# X7A15T-Prog.net
KiCad netlist of a schematic drawn in Altium Designer
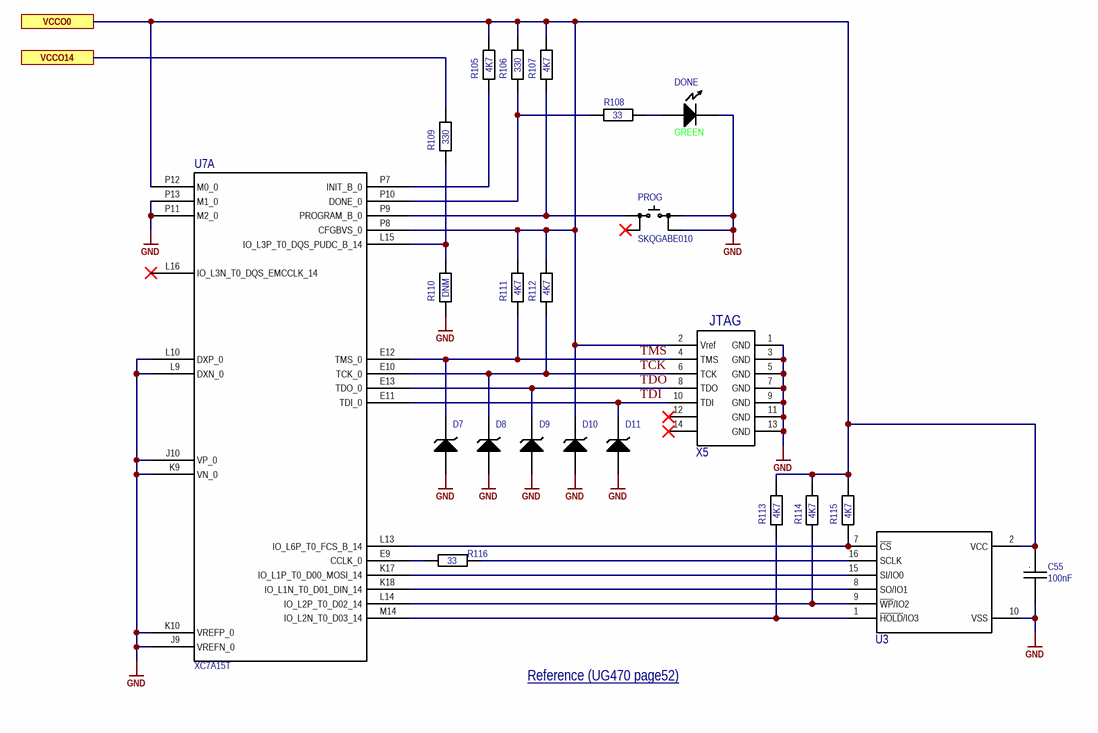
[diagram p0: X7A15T-Prog.SchDoc]

(export (version "E")
  (design (tool "Eeschema 10.0.6"))
  (components
    (comp (ref "C55")
      (value "100nF")
      (footprint "C0402 Reflow")
      (description "CAP CER 0.1UF 25V X7R 0402")
      (fields
        (field (name "TOLERANCE") "±5%")
        (field (name "02. DISTRIBUTOR PART NUMBER") "311-2077-6-ND")
        (field (name "13. CREATED DATE/NAME") "AUG2018/Hören")
      )
      (libsource (lib "chickenfood") (part "C"))
    )
    (comp (ref "D7")
      (value "D")
      (footprint "SOD323")
      (description "TVS DIODE 3.3V 9.5V SOD323")
      (fields
        (field (name "02. DISTRIBUTOR PART NUMBER") "UCLAMP3301DCT-ND")
        (field (name "07. MANUFACTURER  PART NUMBER") "UCLAMP3301D.TCT")
      )
      (libsource (lib "PCB-Tester-Board-V1") (part "UCLAMP3301D.TCT"))
    )
    (comp (ref "D8")
      (value "D")
      (footprint "SOD323")
      (description "TVS DIODE 3.3V 9.5V SOD323")
      (fields
        (field (name "02. DISTRIBUTOR PART NUMBER") "UCLAMP3301DCT-ND")
        (field (name "07. MANUFACTURER  PART NUMBER") "UCLAMP3301D.TCT")
      )
      (libsource (lib "PCB-Tester-Board-V1") (part "UCLAMP3301D.TCT"))
    )
    (comp (ref "D9")
      (value "D")
      (footprint "SOD323")
      (description "TVS DIODE 3.3V 9.5V SOD323")
      (fields
        (field (name "02. DISTRIBUTOR PART NUMBER") "UCLAMP3301DCT-ND")
        (field (name "07. MANUFACTURER  PART NUMBER") "UCLAMP3301D.TCT")
      )
      (libsource (lib "PCB-Tester-Board-V1") (part "UCLAMP3301D.TCT"))
    )
    (comp (ref "D10")
      (value "D")
      (footprint "SOD323")
      (description "TVS DIODE 3.3V 9.5V SOD323")
      (fields
        (field (name "02. DISTRIBUTOR PART NUMBER") "UCLAMP3301DCT-ND")
        (field (name "07. MANUFACTURER  PART NUMBER") "UCLAMP3301D.TCT")
      )
      (libsource (lib "PCB-Tester-Board-V1") (part "UCLAMP3301D.TCT"))
    )
    (comp (ref "D11")
      (value "D")
      (footprint "SOD323")
      (description "TVS DIODE 3.3V 9.5V SOD323")
      (fields
        (field (name "02. DISTRIBUTOR PART NUMBER") "UCLAMP3301DCT-ND")
        (field (name "07. MANUFACTURER  PART NUMBER") "UCLAMP3301D.TCT")
      )
      (libsource (lib "PCB-Tester-Board-V1") (part "UCLAMP3301D.TCT"))
    )
    (comp (ref "DONE")
      (value "D")
      (footprint "L0603G")
      (description "LED GREEN DIFFUSED 0603 SMD")
      (fields
        (field (name "02. DISTRIBUTOR PART NUMBER") "475-2709-6-ND")
        (field (name "07. MANUFACTURER  PART NUMBER") "LG L29K-G2J1-24-Z")
        (field (name "COLOR") "GREEN")
        (field (name "13. CREATED DATE/NAME") "AUG2018/Hören")
      )
      (libsource (lib "chickenfood") (part "LED"))
    )
    (comp (ref "PROG")
      (value "SKQGABE010")
      (footprint "SKQGABE010")
      (description "Tactile Switches 5.2x5.2x1.5mm 160gf")
      (fields (field (name "02. DISTRIBUTOR PART NUMBER") "688-SKQGAB"))
      (libsource (lib "PCB-Tester-Board-V1") (part "PUSH_BTN"))
    )
    (comp (ref "R105")
      (value "4K7")
      (footprint "R0402 Reflow")
      (description "RES SMD 4.7K OHM 1% 1/16W 0402")
      (fields
        (field (name "TOLERANCE") "±1%")
        (field (name "02. DISTRIBUTOR PART NUMBER") "311-4.7KLRDKR-ND")
        (field (name "13. CREATED DATE/NAME") "AUG2018/Hören")
      )
      (libsource (lib "chickenfood") (part "R"))
    )
    (comp (ref "R106")
      (value "330")
      (footprint "R0402 Reflow")
      (description "RES SMD 330 OHM 1% 1/16W 0402")
      (fields
        (field (name "TOLERANCE") "±1%")
        (field (name "02. DISTRIBUTOR PART NUMBER") "311-330LRDKR-ND")
        (field (name "13. CREATED DATE/NAME") "AUG2018/Hören")
      )
      (libsource (lib "chickenfood") (part "R"))
    )
    (comp (ref "R107")
      (value "4K7")
      (footprint "R0402 Reflow")
      (description "RES SMD 4.7K OHM 1% 1/16W 0402")
      (fields
        (field (name "TOLERANCE") "±1%")
        (field (name "02. DISTRIBUTOR PART NUMBER") "311-4.7KLRDKR-ND")
        (field (name "13. CREATED DATE/NAME") "AUG2018/Hören")
      )
      (libsource (lib "chickenfood") (part "R"))
    )
    (comp (ref "R108")
      (value "33")
      (footprint "R0402 Reflow")
      (description "RES SMD 33 OHM 1% 1/16W 0402")
      (fields
        (field (name "TOLERANCE") "±1%")
        (field (name "02. DISTRIBUTOR PART NUMBER") "311-33.0LRDKR-ND")
        (field (name "13. CREATED DATE/NAME") "AUG2018/Hören")
      )
      (libsource (lib "PCB-Tester-Board-V1") (part "R_19"))
    )
    (comp (ref "R109")
      (value "330")
      (footprint "R0402 Reflow")
      (description "RES SMD 330 OHM 1% 1/16W 0402")
      (fields
        (field (name "TOLERANCE") "±1%")
        (field (name "02. DISTRIBUTOR PART NUMBER") "311-330LRDKR-ND")
        (field (name "13. CREATED DATE/NAME") "AUG2018/Hören")
      )
      (libsource (lib "chickenfood") (part "R"))
    )
    (comp (ref "R110")
      (value "DNM")
      (footprint "R0402 Reflow")
      (description "RES SMD 330 OHM 1% 1/16W 0402")
      (fields
        (field (name "TOLERANCE") "±1%")
        (field (name "02. DISTRIBUTOR PART NUMBER") "311-330LRDKR-ND")
        (field (name "13. CREATED DATE/NAME") "AUG2018/Hören")
      )
      (libsource (lib "chickenfood") (part "R"))
    )
    (comp (ref "R111")
      (value "4K7")
      (footprint "R0402 Reflow")
      (description "RES SMD 4.7K OHM 1% 1/16W 0402")
      (fields
        (field (name "TOLERANCE") "±1%")
        (field (name "02. DISTRIBUTOR PART NUMBER") "311-4.7KLRDKR-ND")
        (field (name "13. CREATED DATE/NAME") "AUG2018/Hören")
      )
      (libsource (lib "chickenfood") (part "R"))
    )
    (comp (ref "R112")
      (value "4K7")
      (footprint "R0402 Reflow")
      (description "RES SMD 4.7K OHM 1% 1/16W 0402")
      (fields
        (field (name "TOLERANCE") "±1%")
        (field (name "02. DISTRIBUTOR PART NUMBER") "311-4.7KLRDKR-ND")
        (field (name "13. CREATED DATE/NAME") "AUG2018/Hören")
      )
      (libsource (lib "chickenfood") (part "R"))
    )
    (comp (ref "R113")
      (value "4K7")
      (footprint "R0402 Reflow")
      (description "RES SMD 4.7K OHM 1% 1/16W 0402")
      (fields
        (field (name "TOLERANCE") "±1%")
        (field (name "02. DISTRIBUTOR PART NUMBER") "311-4.7KLRDKR-ND")
        (field (name "13. CREATED DATE/NAME") "AUG2018/Hören")
      )
      (libsource (lib "chickenfood") (part "R"))
    )
    (comp (ref "R114")
      (value "4K7")
      (footprint "R0402 Reflow")
      (description "RES SMD 4.7K OHM 1% 1/16W 0402")
      (fields
        (field (name "TOLERANCE") "±1%")
        (field (name "02. DISTRIBUTOR PART NUMBER") "311-4.7KLRDKR-ND")
        (field (name "13. CREATED DATE/NAME") "AUG2018/Hören")
      )
      (libsource (lib "chickenfood") (part "R"))
    )
    (comp (ref "R115")
      (value "4K7")
      (footprint "R0402 Reflow")
      (description "RES SMD 4.7K OHM 1% 1/16W 0402")
      (fields
        (field (name "TOLERANCE") "±1%")
        (field (name "02. DISTRIBUTOR PART NUMBER") "311-4.7KLRDKR-ND")
        (field (name "13. CREATED DATE/NAME") "AUG2018/Hören")
      )
      (libsource (lib "chickenfood") (part "R"))
    )
    (comp (ref "R116")
      (value "33")
      (footprint "R0402 Reflow")
      (description "RES SMD 33 OHM 1% 1/16W 0402")
      (fields
        (field (name "TOLERANCE") "±1%")
        (field (name "02. DISTRIBUTOR PART NUMBER") "311-33.0LRDKR-ND")
        (field (name "13. CREATED DATE/NAME") "AUG2018/Hören")
      )
      (libsource (lib "PCB-Tester-Board-V1") (part "R_19"))
    )
    (comp (ref "U3")
      (value "U")
      (footprint "SOICW-16")
      (description "IC FLASH 128M SPI 133MHZ 16SOIC")
      (fields (field (name "02. DISTRIBUTOR PART NUMBER") "1274-1000-ND"))
      (libsource (lib "PCB-Tester-Board-V1") (part "S25FL128SAGMFI000"))
    )
    (comp (ref "U7")
      (value "U")
      (footprint "XC7A15T-1CSG324C")
      (description "XC7A15T-1CSG324C")
      (fields (field (name "MFR") "XILINX") (field (name "NICNAME") "XC7A15T"))
      (libsource (lib "PCB-Tester-Board-V1") (part "XC7A15T-CS324"))
    )
    (comp (ref "X5")
      (value "X")
      (footprint "LTMM-107-02-F-D")
      (description "CONN HEADER VERT 14POS 2MM")
      (fields
        (field (name "02. DISTRIBUTOR PART NUMBER") "LTMM-107-02-F-D-ND")
        (field (name "07. MANUFACTURER  PART NUMBER") "LTMM-107-02-F-D")
        (field (name "NICKNAME") "JTAG")
        (field (name "13. CREATED DATE/NAME") "??? / Hören")
      )
      (libsource (lib "Connectors") (part "LTMM-107-02-F-D"))
    )
  )
  (nets
    (net (code "1") (name "/TCK") (class "Default")
      (node (ref "D8") (pin "2") (pinfunction "C_2") (pintype "passive"))
      (node (ref "R112") (pin "1") (pinfunction "1_1") (pintype "passive"))
      (node (ref "U7") (pin "E10") (pinfunction "TCK_0_E10") (pintype "passive"))
      (node (ref "X5") (pin "6") (pinfunction "TCK_6") (pintype "passive"))
    )
    (net (code "2") (name "/TDI") (class "Default")
      (node (ref "D11") (pin "2") (pinfunction "C_2") (pintype "passive"))
      (node (ref "U7") (pin "E11") (pinfunction "TDI_0_E11") (pintype "passive"))
      (node (ref "X5") (pin "10") (pinfunction "TDI_10") (pintype "passive"))
    )
    (net (code "3") (name "/TDO") (class "Default")
      (node (ref "D9") (pin "2") (pinfunction "C_2") (pintype "passive"))
      (node (ref "U7") (pin "E13") (pinfunction "TDO_0_E13") (pintype "passive"))
      (node (ref "X5") (pin "8") (pinfunction "TDO_8") (pintype "passive"))
    )
    (net (code "4") (name "/TMS") (class "Default")
      (node (ref "D7") (pin "2") (pinfunction "C_2") (pintype "passive"))
      (node (ref "R111") (pin "1") (pinfunction "1_1") (pintype "passive"))
      (node (ref "U7") (pin "E12") (pinfunction "TMS_0_E12") (pintype "passive"))
      (node (ref "X5") (pin "4") (pinfunction "TMS_4") (pintype "passive"))
    )
    (net (code "5") (name "/VCCO0") (class "Default")
      (node (ref "C55") (pin "1") (pinfunction "1_1") (pintype "passive"))
      (node (ref "D10") (pin "2") (pinfunction "C_2") (pintype "passive"))
      (node (ref "R105") (pin "2") (pinfunction "2_2") (pintype "passive"))
      (node (ref "R106") (pin "2") (pinfunction "2_2") (pintype "passive"))
      (node (ref "R107") (pin "2") (pinfunction "2_2") (pintype "passive"))
      (node (ref "R111") (pin "2") (pinfunction "2_2") (pintype "passive"))
      (node (ref "R112") (pin "2") (pinfunction "2_2") (pintype "passive"))
      (node (ref "R113") (pin "2") (pinfunction "2_2") (pintype "passive"))
      (node (ref "R114") (pin "2") (pinfunction "2_2") (pintype "passive"))
      (node (ref "R115") (pin "2") (pinfunction "2_2") (pintype "passive"))
      (node (ref "U3") (pin "2") (pinfunction "VCC_2") (pintype "passive"))
      (node (ref "U7") (pin "P12") (pinfunction "M0_0_P12") (pintype "passive"))
      (node (ref "U7") (pin "P8") (pinfunction "CFGBVS_0_P8") (pintype "passive"))
      (node (ref "X5") (pin "2") (pinfunction "Vref_2") (pintype "passive"))
    )
    (net (code "6") (name "/VCCO14") (class "Default")
      (node (ref "R109") (pin "2") (pinfunction "2_2") (pintype "passive"))
    )
    (net (code "7") (name "GND") (class "Default")
      (node (ref "C55") (pin "2") (pinfunction "2_2") (pintype "passive"))
      (node (ref "D10") (pin "1") (pinfunction "A_1") (pintype "passive"))
      (node (ref "D11") (pin "1") (pinfunction "A_1") (pintype "passive"))
      (node (ref "D7") (pin "1") (pinfunction "A_1") (pintype "passive"))
      (node (ref "D8") (pin "1") (pinfunction "A_1") (pintype "passive"))
      (node (ref "D9") (pin "1") (pinfunction "A_1") (pintype "passive"))
      (node (ref "DONE") (pin "2") (pinfunction "Cathode_2") (pintype "passive"))
      (node (ref "PROG") (pin "3") (pinfunction "3_3") (pintype "passive"))
      (node (ref "PROG") (pin "4") (pinfunction "4_4") (pintype "passive"))
      (node (ref "R110") (pin "1") (pinfunction "1_1") (pintype "passive"))
      (node (ref "U3") (pin "10") (pinfunction "VSS_10") (pintype "passive"))
      (node (ref "U7") (pin "J10") (pinfunction "VP_0_J10") (pintype "passive"))
      (node (ref "U7") (pin "J9") (pinfunction "VREFN_0_J9") (pintype "passive"))
      (node (ref "U7") (pin "K10") (pinfunction "VREFP_0_K10") (pintype "passive"))
      (node (ref "U7") (pin "K9") (pinfunction "VN_0_K9") (pintype "passive"))
      (node (ref "U7") (pin "L10") (pinfunction "DXP_0_L10") (pintype "passive"))
      (node (ref "U7") (pin "L9") (pinfunction "DXN_0_L9") (pintype "passive"))
      (node (ref "U7") (pin "P11") (pinfunction "M2_0_P11") (pintype "passive"))
      (node (ref "U7") (pin "P13") (pinfunction "M1_0_P13") (pintype "passive"))
      (node (ref "X5") (pin "1") (pinfunction "GND_1") (pintype "passive"))
      (node (ref "X5") (pin "11") (pinfunction "GND_11") (pintype "passive"))
      (node (ref "X5") (pin "13") (pinfunction "GND_13") (pintype "passive"))
      (node (ref "X5") (pin "3") (pinfunction "GND_3") (pintype "passive"))
      (node (ref "X5") (pin "5") (pinfunction "GND_5") (pintype "passive"))
      (node (ref "X5") (pin "7") (pinfunction "GND_7") (pintype "passive"))
      (node (ref "X5") (pin "9") (pinfunction "GND_9") (pintype "passive"))
    )
    (net (code "8") (name "Net-(DONE-Anode)") (class "Default")
      (node (ref "DONE") (pin "1") (pinfunction "Anode_1") (pintype "passive"))
      (node (ref "R108") (pin "2") (pinfunction "2_2") (pintype "passive"))
    )
    (net (code "9") (name "Net-(U3-SCLK)") (class "Default")
      (node (ref "R116") (pin "2") (pinfunction "2_2") (pintype "passive"))
      (node (ref "U3") (pin "16") (pinfunction "SCLK_16") (pintype "passive"))
    )
    (net (code "10") (name "Net-(U3-SI{slash}IO0)") (class "Default")
      (node (ref "U3") (pin "15") (pinfunction "SI/IO0_15") (pintype "passive"))
      (node (ref "U7") (pin "K17") (pinfunction "IO_L1P_T0_D00_MOSI_14_K17") (pintype "passive"))
    )
    (net (code "11") (name "Net-(U3-SO{slash}IO1)") (class "Default")
      (node (ref "U3") (pin "8") (pinfunction "SO/IO1_8") (pintype "passive"))
      (node (ref "U7") (pin "K18") (pinfunction "IO_L1N_T0_D01_DIN_14_K18") (pintype "passive"))
    )
    (net (code "12") (name "Net-(U3-~{CS})") (class "Default")
      (node (ref "R115") (pin "1") (pinfunction "1_1") (pintype "passive"))
      (node (ref "U3") (pin "7") (pinfunction "~{CS}_7") (pintype "passive"))
      (node (ref "U7") (pin "L13") (pinfunction "IO_L6P_T0_FCS_B_14_L13") (pintype "passive"))
    )
    (net (code "13") (name "Net-(U3-~{HOLD}{slash}IO3)") (class "Default")
      (node (ref "R113") (pin "1") (pinfunction "1_1") (pintype "passive"))
      (node (ref "U3") (pin "1") (pinfunction "~{HOLD}/IO3_1") (pintype "passive"))
      (node (ref "U7") (pin "M14") (pinfunction "IO_L2N_T0_D03_14_M14") (pintype "passive"))
    )
    (net (code "14") (name "Net-(U3-~{WP}{slash}IO2)") (class "Default")
      (node (ref "R114") (pin "1") (pinfunction "1_1") (pintype "passive"))
      (node (ref "U3") (pin "9") (pinfunction "~{WP}/IO2_9") (pintype "passive"))
      (node (ref "U7") (pin "L14") (pinfunction "IO_L2P_T0_D02_14_L14") (pintype "passive"))
    )
    (net (code "15") (name "Net-(U7A-CCLK_0)") (class "Default")
      (node (ref "R116") (pin "1") (pinfunction "1_1") (pintype "passive"))
      (node (ref "U7") (pin "E9") (pinfunction "CCLK_0_E9") (pintype "passive"))
    )
    (net (code "16") (name "Net-(U7A-DONE_0)") (class "Default")
      (node (ref "R106") (pin "1") (pinfunction "1_1") (pintype "passive"))
      (node (ref "R108") (pin "1") (pinfunction "1_1") (pintype "passive"))
      (node (ref "U7") (pin "P10") (pinfunction "DONE_0_P10") (pintype "passive"))
    )
    (net (code "17") (name "Net-(U7A-INIT_B_0)") (class "Default")
      (node (ref "R105") (pin "1") (pinfunction "1_1") (pintype "passive"))
      (node (ref "U7") (pin "P7") (pinfunction "INIT_B_0_P7") (pintype "passive"))
    )
    (net (code "18") (name "Net-(U7A-IO_L3P_T0_DQS_PUDC_B_14)") (class "Default")
      (node (ref "R109") (pin "1") (pinfunction "1_1") (pintype "passive"))
      (node (ref "R110") (pin "2") (pinfunction "2_2") (pintype "passive"))
      (node (ref "U7") (pin "L15") (pinfunction "IO_L3P_T0_DQS_PUDC_B_14_L15") (pintype "passive"))
    )
    (net (code "19") (name "Net-(U7A-PROGRAM_B_0)") (class "Default")
      (node (ref "PROG") (pin "1") (pinfunction "1_1") (pintype "passive"))
      (node (ref "R107") (pin "1") (pinfunction "1_1") (pintype "passive"))
      (node (ref "U7") (pin "P9") (pinfunction "PROGRAM_B_0_P9") (pintype "passive"))
    )
    (net (code "20") (name "unconnected-(PROG-Pad2)") (class "Default")
      (node (ref "PROG") (pin "2") (pinfunction "2_2") (pintype "passive+no_connect"))
    )
    (net (code "21") (name "unconnected-(U7A-IO_L3N_T0_DQS_EMCCLK_14-PadL16)") (class "Default")
      (node (ref "U7") (pin "L16") (pinfunction "IO_L3N_T0_DQS_EMCCLK_14_L16") (pintype "passive+no_connect"))
    )
    (net (code "22") (name "unconnected-(X5-Pad12)") (class "Default")
      (node (ref "X5") (pin "12") (pinfunction "12_12") (pintype "passive+no_connect"))
    )
    (net (code "23") (name "unconnected-(X5-Pad14)") (class "Default")
      (node (ref "X5") (pin "14") (pinfunction "14_14") (pintype "passive+no_connect"))
    )
  )
)
